# TFD-50RA.net
KiCad netlist of a schematic drawn in Altium Designer
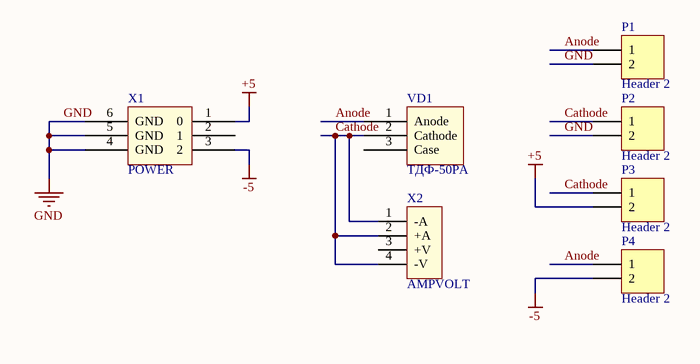
[diagram p0: TFD-50RA.SchDoc]

(export (version "E")
  (design (tool "Eeschema 10.0.6"))
  (components
    (comp (ref "P1")
      (value "Header 2")
      (footprint "HDR1X2")
      (description "Header, 2-Pin")
      (fields (field (name "PUBLISHER") "Altium Limited"))
      (libsource (lib "Miscellaneous Connectors") (part "Header 2"))
    )
    (comp (ref "P2")
      (value "Header 2")
      (footprint "HDR1X2")
      (description "Header, 2-Pin")
      (fields (field (name "PUBLISHER") "Altium Limited"))
      (libsource (lib "Miscellaneous Connectors") (part "Header 2"))
    )
    (comp (ref "P3")
      (value "Header 2")
      (footprint "HDR1X2")
      (description "Header, 2-Pin")
      (fields (field (name "PUBLISHER") "Altium Limited"))
      (libsource (lib "Miscellaneous Connectors") (part "Header 2"))
    )
    (comp (ref "P4")
      (value "Header 2")
      (footprint "HDR1X2")
      (description "Header, 2-Pin")
      (fields (field (name "PUBLISHER") "Altium Limited"))
      (libsource (lib "Miscellaneous Connectors") (part "Header 2"))
    )
    (comp (ref "VD1")
      (value "ТДФ-50РА")
      (footprint "aab_Active:ТДФ-50РА")
      (libsource (lib "aab_Schlib") (part "ТДФ-50РА"))
    )
    (comp (ref "X1") (value "POWER") (footprint "POWER") (libsource (lib "vpl_Schlib") (part "POWER")))
    (comp (ref "X2")
      (value "AMPVOLT")
      (footprint "AMP_VOLTMETER")
      (libsource (lib "vpl_Schlib") (part "AMP_VOLTMETER"))
    )
  )
  (nets
    (net (code "1") (name "+5") (class "Default")
      (node (ref "P3") (pin "2") (pinfunction "2_2") (pintype "passive"))
      (node (ref "X1") (pin "1") (pinfunction "0_1") (pintype "passive"))
    )
    (net (code "2") (name "-5") (class "Default")
      (node (ref "P4") (pin "2") (pinfunction "2_2") (pintype "passive"))
      (node (ref "X1") (pin "3") (pinfunction "2_3") (pintype "passive"))
    )
    (net (code "3") (name "/Anode") (class "Default")
      (node (ref "P1") (pin "1") (pinfunction "1_1") (pintype "passive"))
      (node (ref "P4") (pin "1") (pinfunction "1_1") (pintype "passive"))
      (node (ref "VD1") (pin "1") (pinfunction "Anode_1") (pintype "passive"))
    )
    (net (code "4") (name "/Cathode") (class "Default")
      (node (ref "P2") (pin "1") (pinfunction "1_1") (pintype "passive"))
      (node (ref "P3") (pin "1") (pinfunction "1_1") (pintype "passive"))
      (node (ref "VD1") (pin "2") (pinfunction "Cathode_2") (pintype "passive"))
      (node (ref "X2") (pin "1") (pinfunction "-A_1") (pintype "passive"))
      (node (ref "X2") (pin "2") (pinfunction "+A_2") (pintype "passive"))
      (node (ref "X2") (pin "4") (pinfunction "-V_4") (pintype "passive"))
    )
    (net (code "5") (name "GND") (class "Default")
      (node (ref "P1") (pin "2") (pinfunction "2_2") (pintype "passive"))
      (node (ref "P2") (pin "2") (pinfunction "2_2") (pintype "passive"))
      (node (ref "X1") (pin "4") (pinfunction "GND_4") (pintype "passive"))
      (node (ref "X1") (pin "5") (pinfunction "GND_5") (pintype "passive"))
      (node (ref "X1") (pin "6") (pinfunction "GND_6") (pintype "passive"))
    )
    (net (code "6") (name "unconnected-(VD1-Case-Pad3)") (class "Default")
      (node (ref "VD1") (pin "3") (pinfunction "Case_3") (pintype "passive"))
    )
    (net (code "7") (name "unconnected-(X1-1-Pad2)") (class "Default")
      (node (ref "X1") (pin "2") (pinfunction "1_2") (pintype "passive"))
    )
    (net (code "8") (name "unconnected-(X2-+V-Pad3)") (class "Default")
      (node (ref "X2") (pin "3") (pinfunction "+V_3") (pintype "passive"))
    )
  )
)
